# Pedal_board.net
KiCad netlist of a schematic drawn in EAGLE
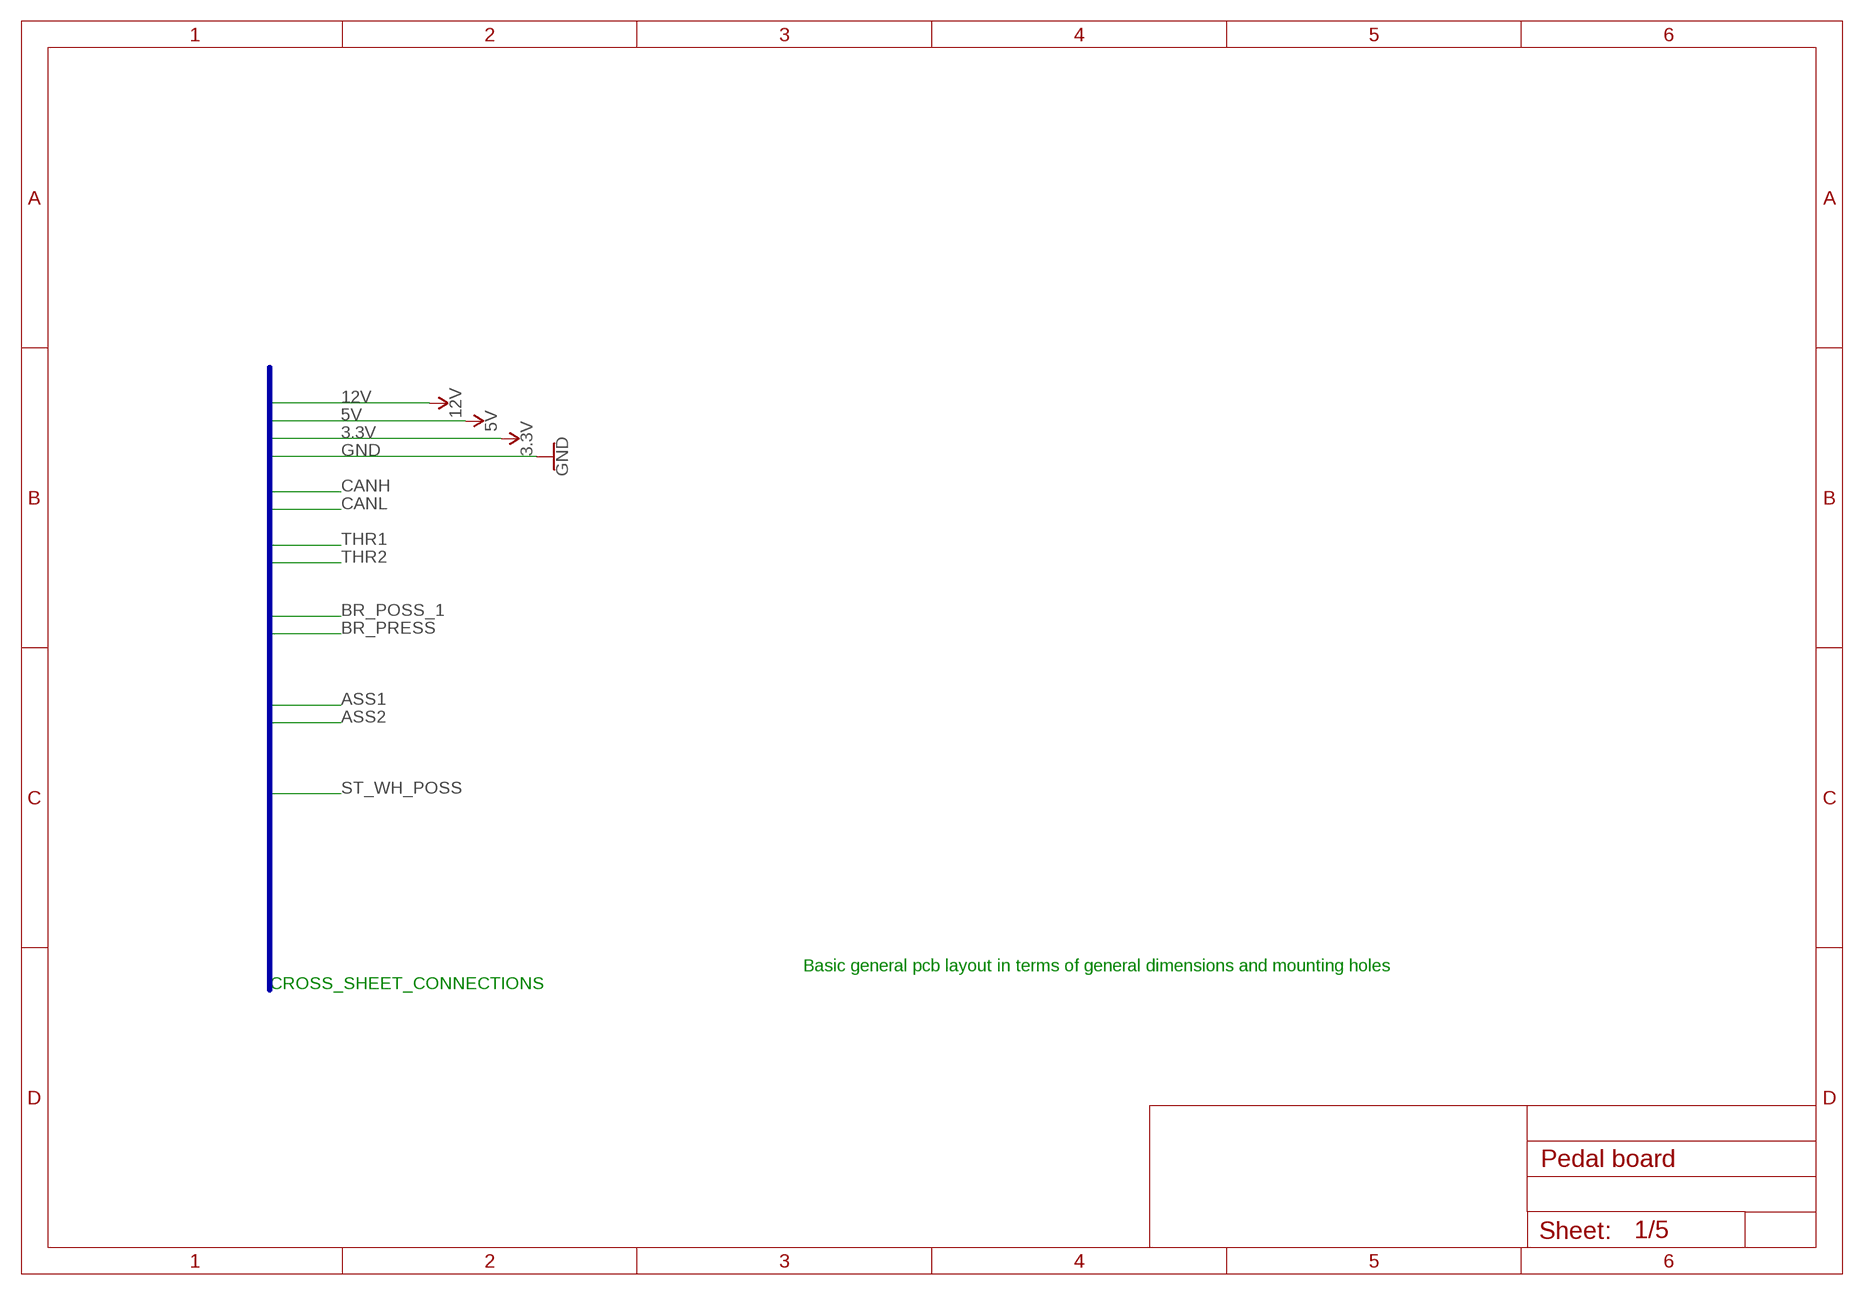
[diagram p0: schematic, sheet 1]
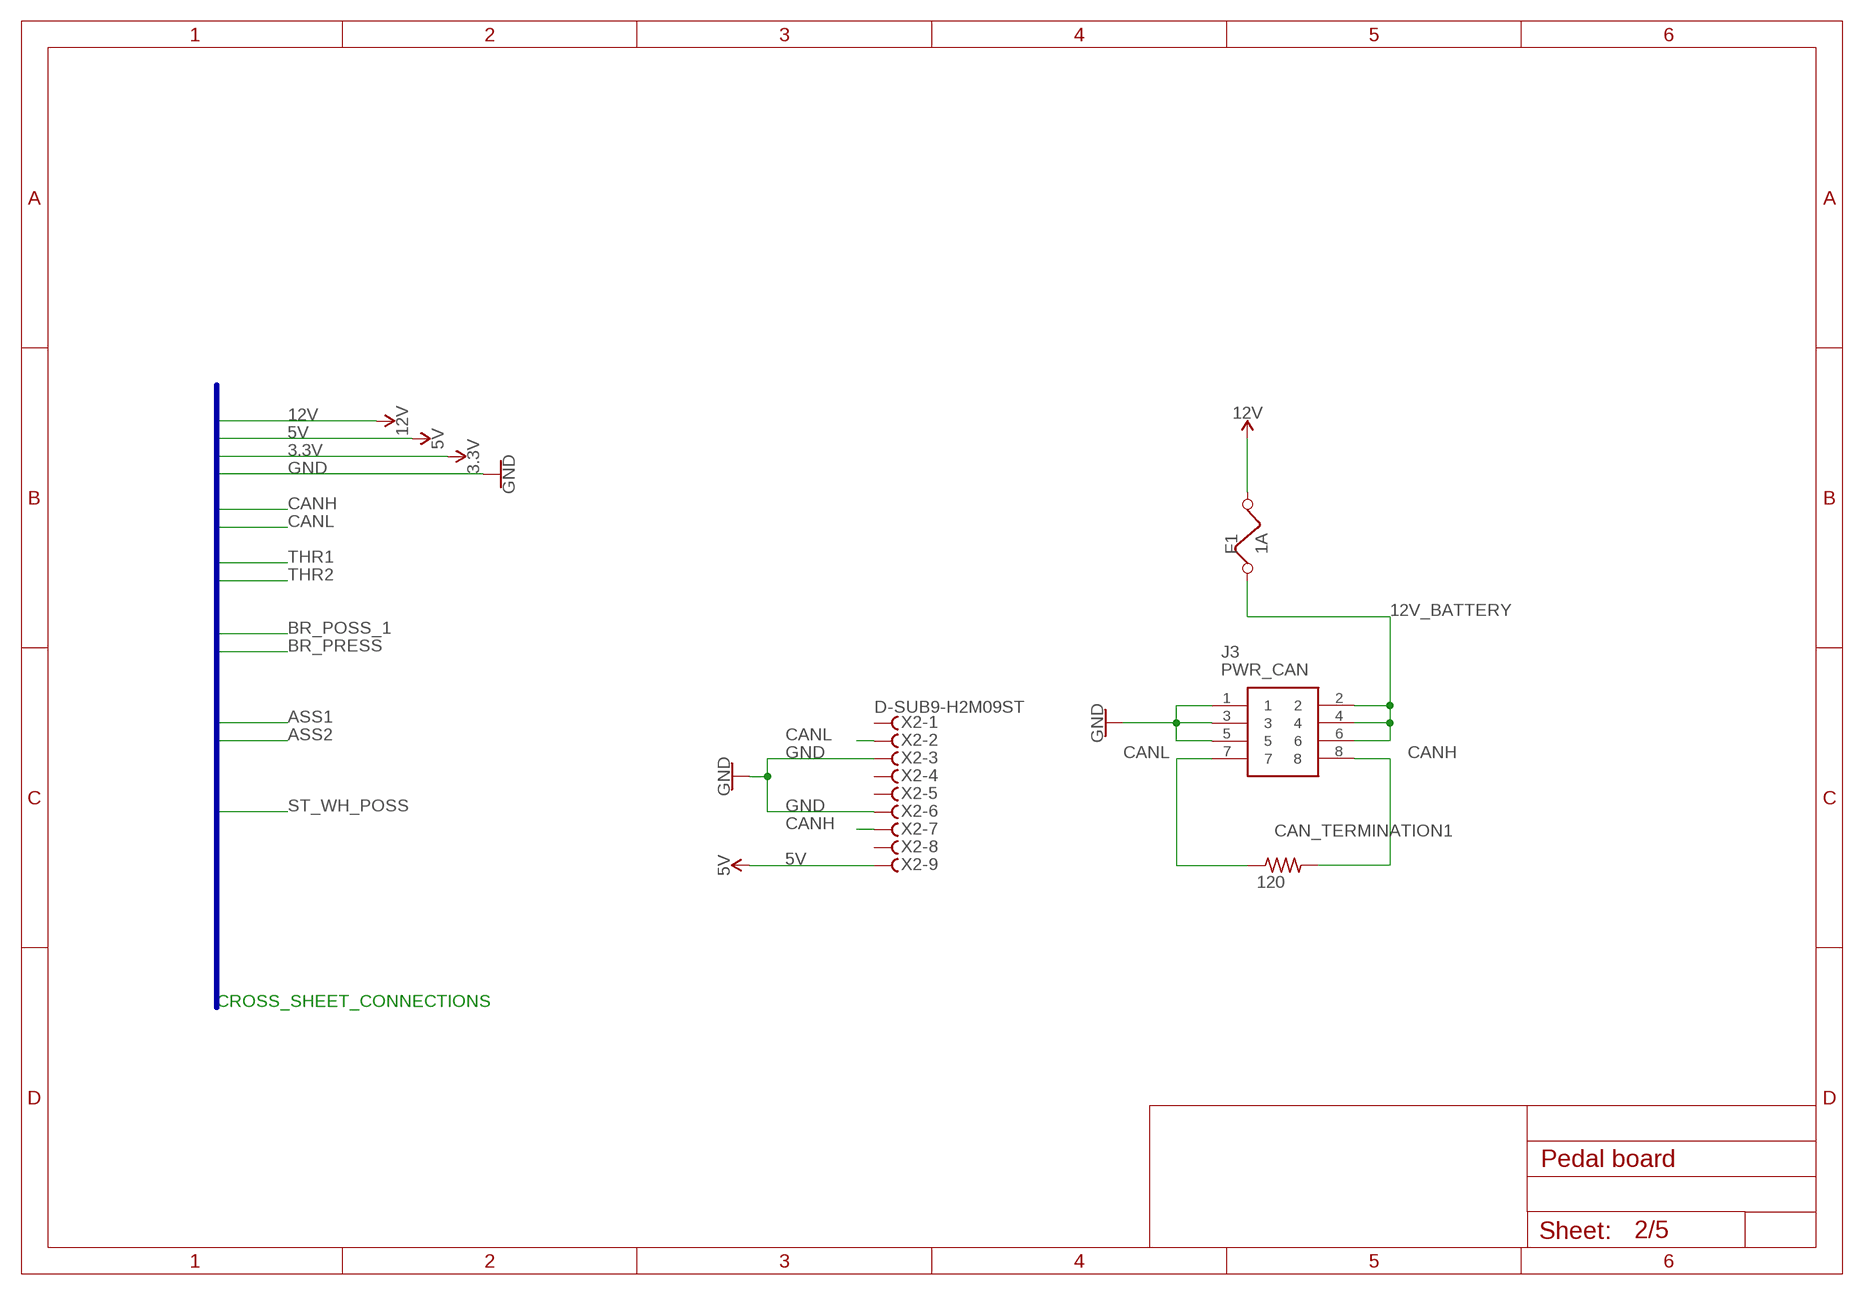
[diagram p1: schematic, sheet 2]
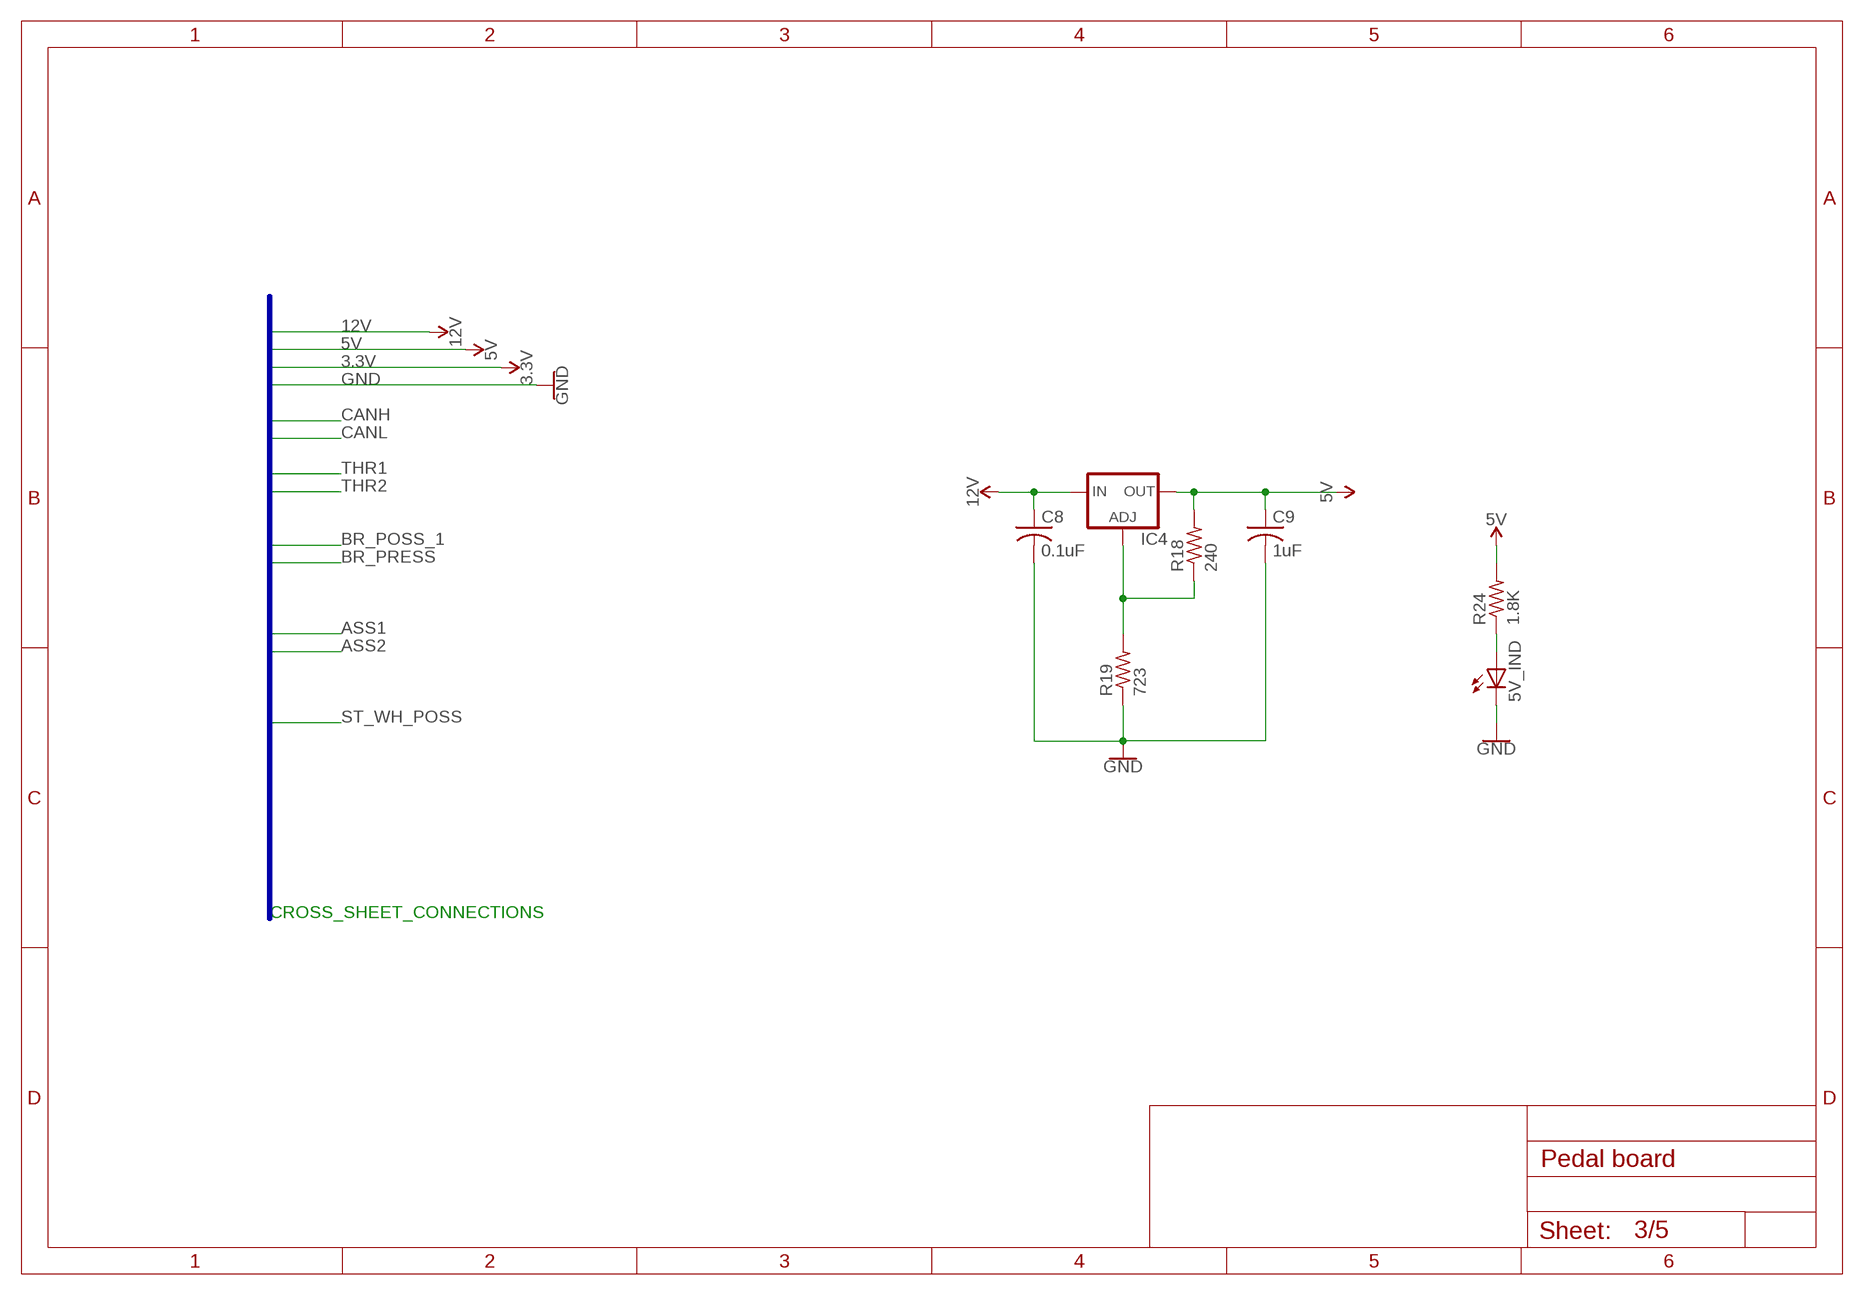
[diagram p2: schematic, sheet 3]
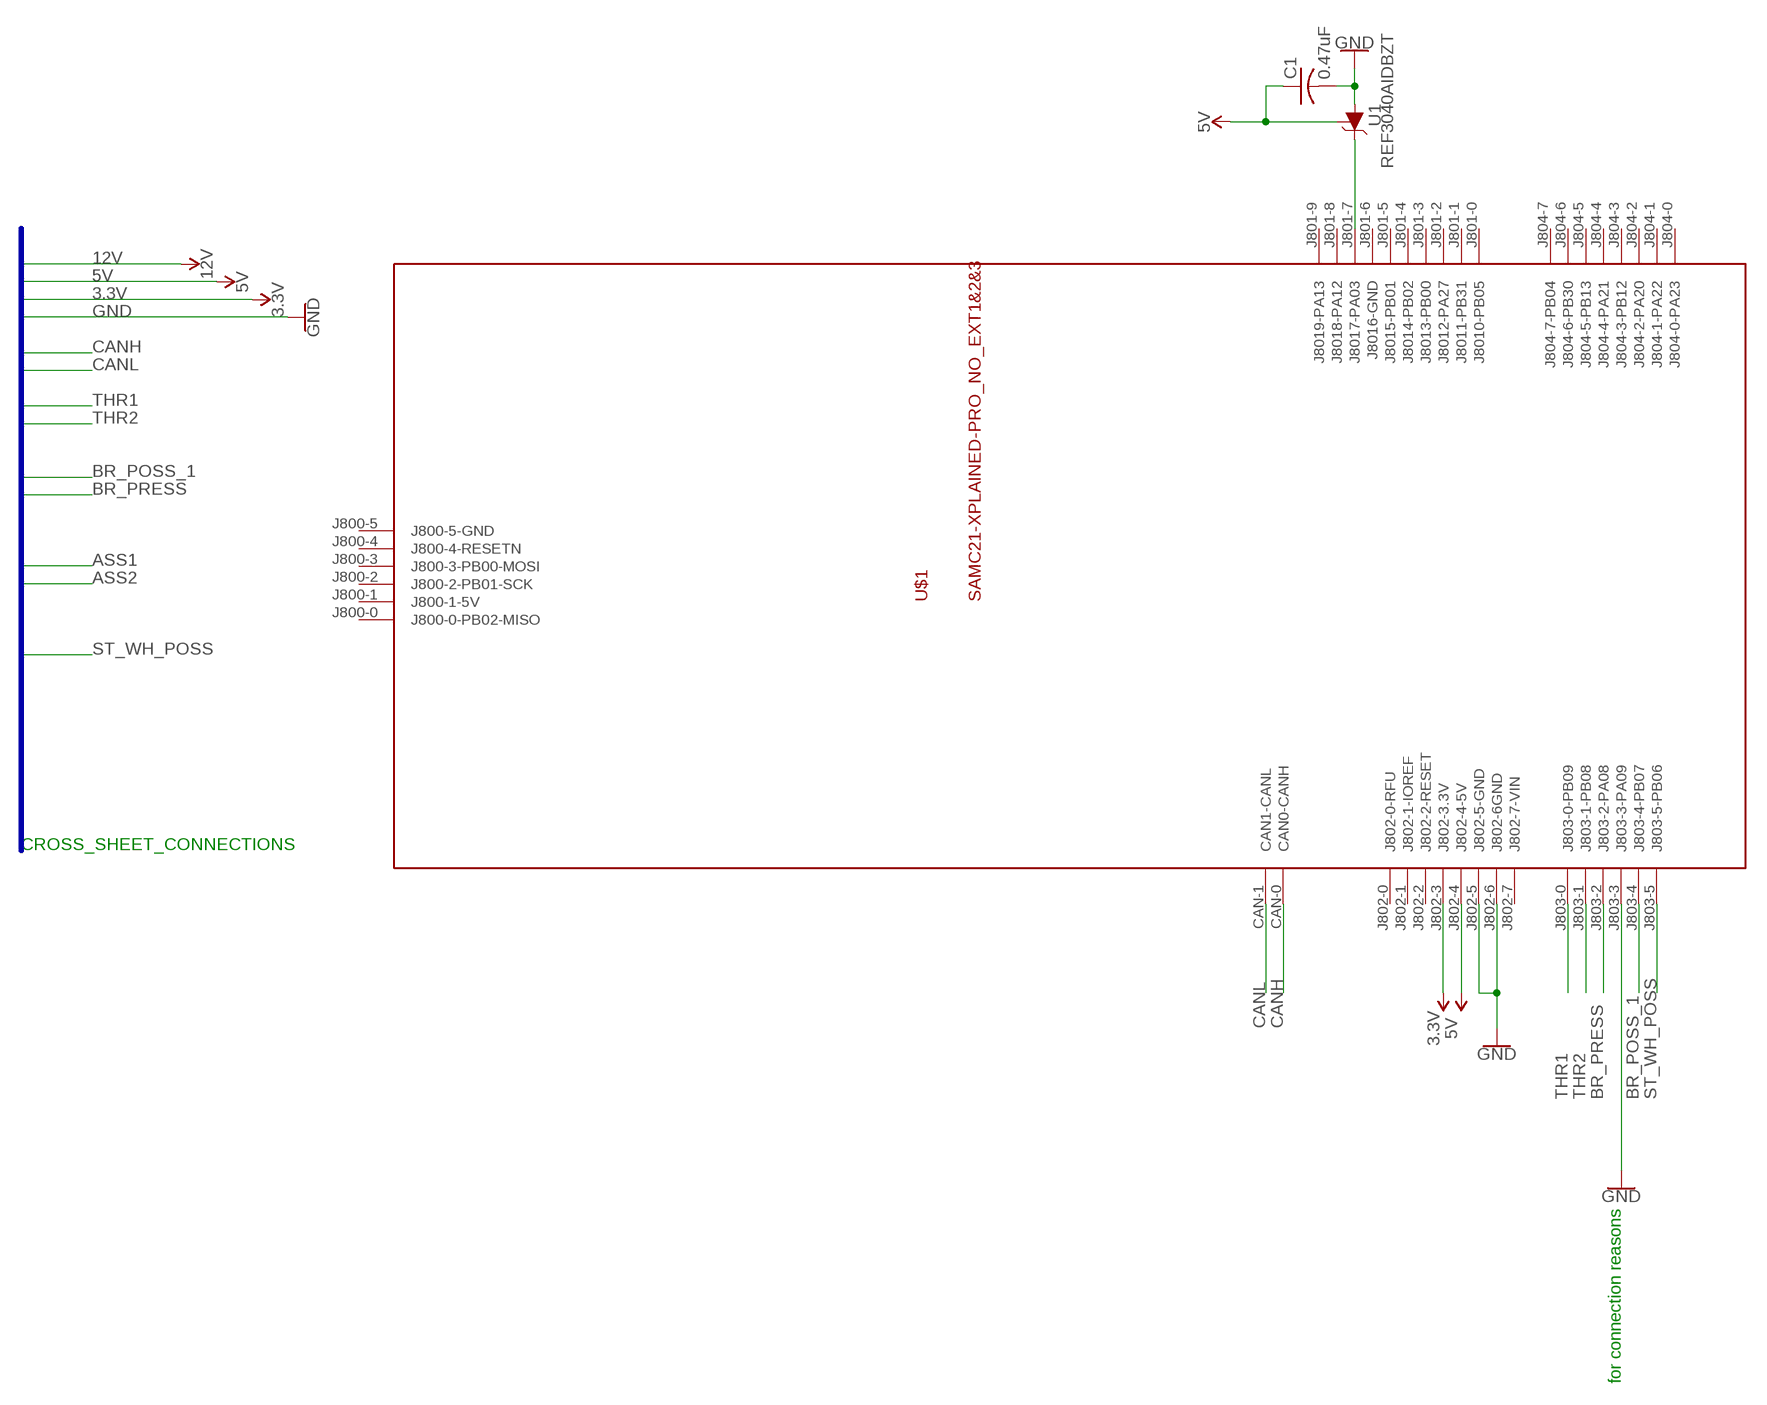
[diagram p3: schematic, sheet 4]
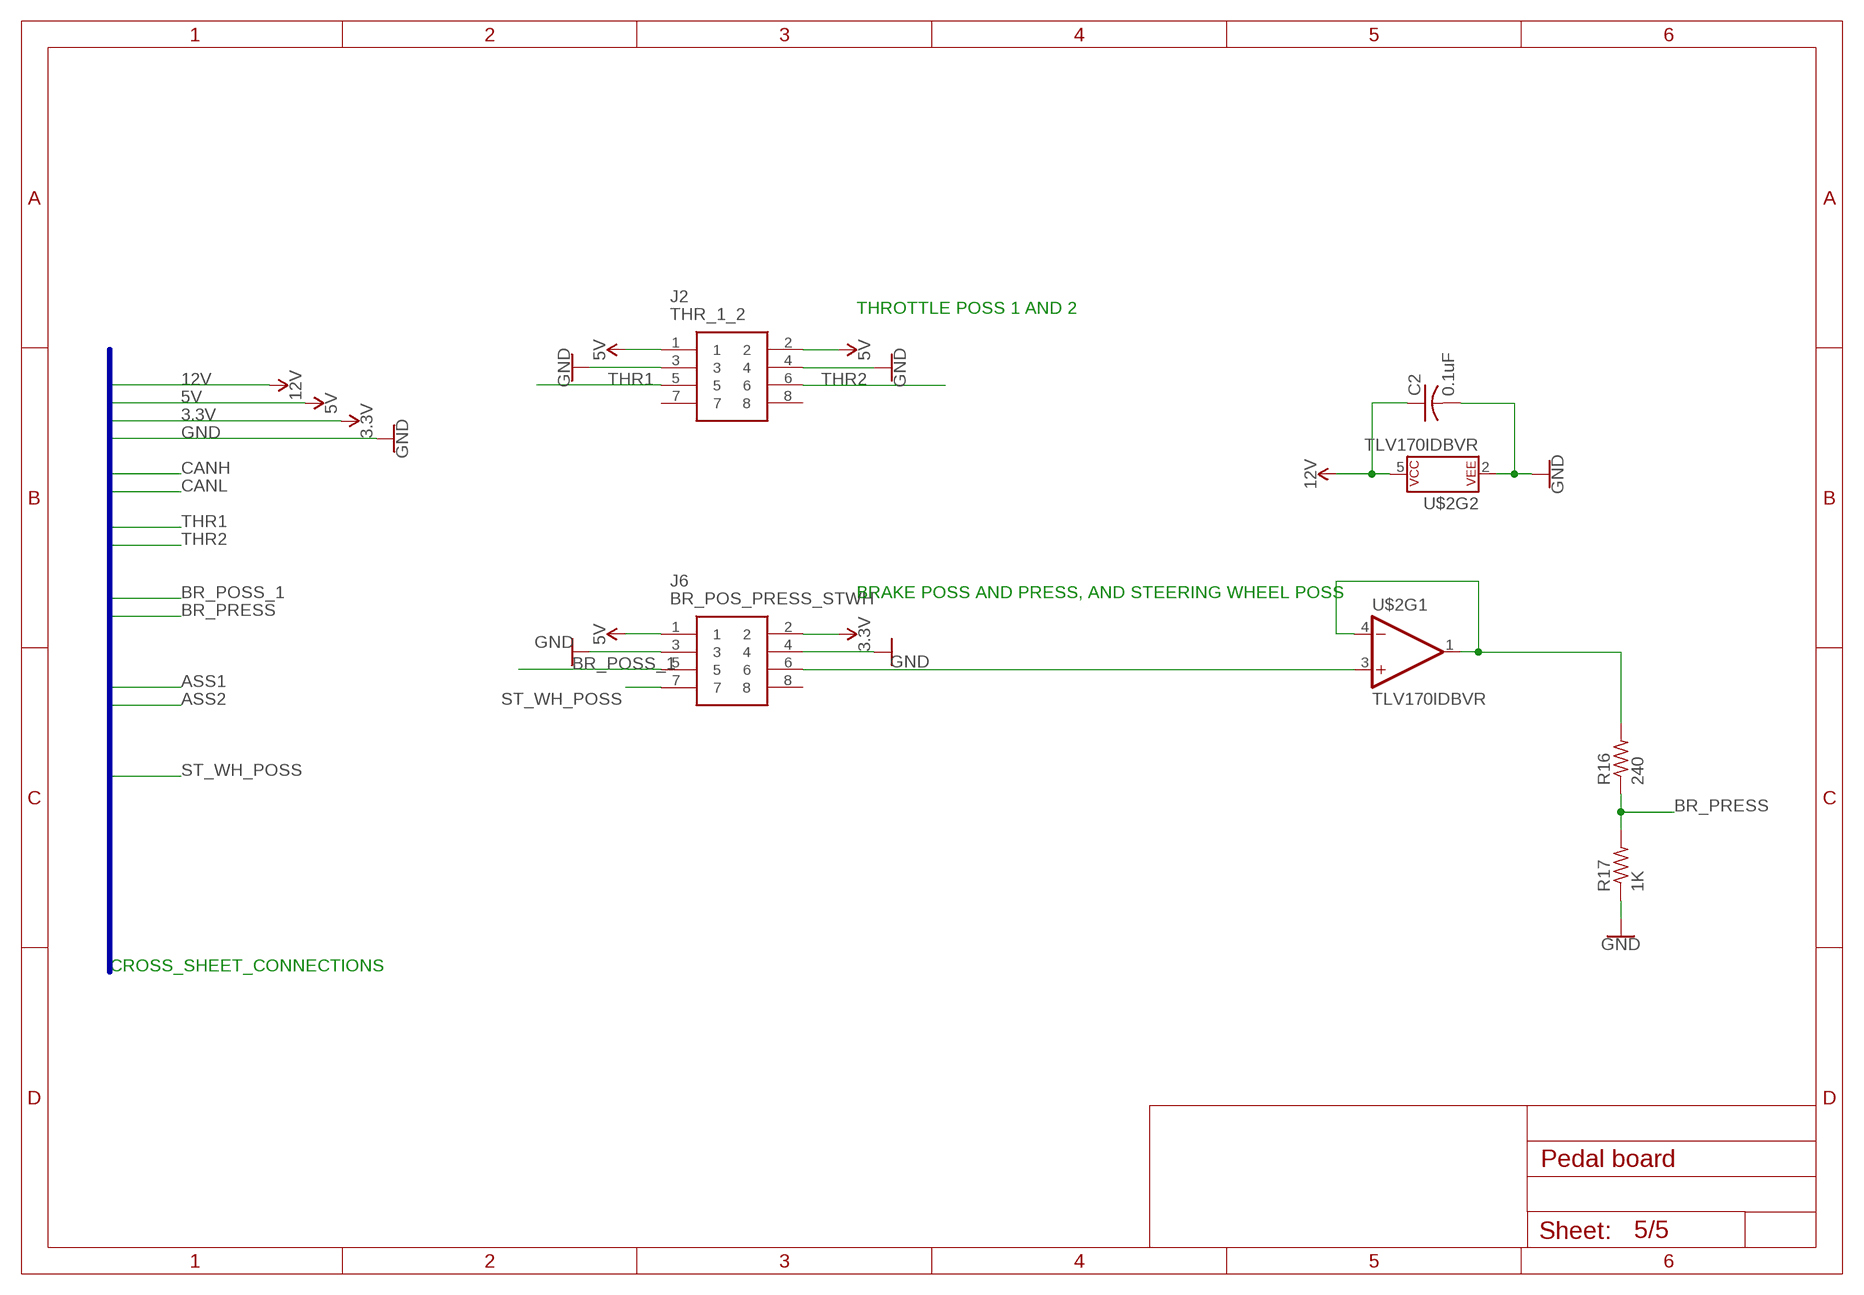
[diagram p4: schematic, sheet 5]

(export (version "E")
  (design (tool "Eeschema 10.0.6"))
  (components
    (comp (ref "5V_IND")
      (value "LED3MM")
      (footprint "eagle-import:LED3MM")
      (libsource (lib "eagle-import") (part "LED3MM"))
    )
    (comp (ref "C8")
      (value "0.1uF")
      (footprint "eagle-import:C050-025X075")
      (libsource (lib "eagle-import") (part "C-US050-025X075"))
    )
    (comp (ref "C9")
      (value "1uF")
      (footprint "eagle-import:C050-025X075")
      (libsource (lib "eagle-import") (part "C-US050-025X075"))
    )
    (comp (ref "IC4")
      (value "LM317TS")
      (footprint "eagle-import:317TS")
      (libsource (lib "eagle-import") (part "LM317TS"))
    )
    (comp (ref "R18")
      (value "240")
      (footprint "eagle-import:R0805")
      (libsource (lib "eagle-import") (part "R-US_R0805"))
    )
    (comp (ref "R19")
      (value "723")
      (footprint "eagle-import:R0805")
      (libsource (lib "eagle-import") (part "R-US_R0805"))
    )
    (comp (ref "R24")
      (value "1.8K")
      (footprint "eagle-import:R0805")
      (libsource (lib "eagle-import") (part "R-US_R0805"))
    )
    (comp (ref "C1")
      (value "0.47uF")
      (footprint "eagle-import:C050-024X044")
      (libsource (lib "eagle-import") (part "C-US050-024X044"))
    )
    (comp (ref "U$1")
      (value "SAMC21-XPLAINED-PRO_NO_EXT1&2&3")
      (footprint "eagle-import:SAMC21-XPLAINED-PRO_NO_EXT1&2&3")
      (libsource (lib "eagle-import") (part "SAMC21-XPLAINED-PRO_NO_EXT1&2&3"))
    )
    (comp (ref "U1")
      (value "REF3040AIDBZT")
      (footprint "eagle-import:SOT23-3")
      (libsource (lib "eagle-import") (part "LM4051"))
    )
    (comp (ref "C2")
      (value "0.1uF")
      (footprint "eagle-import:C050-024X044")
      (libsource (lib "eagle-import") (part "C-US050-024X044"))
    )
    (comp (ref "J2")
      (value "THR_1_2")
      (footprint "eagle-import:HDRV8W64P254_2X4_1778X895X915P")
      (fields
        (field (name "MANUFACTURER_PART_NUMBER") "T821108A1S100CEU")
        (field (name "RS_PART_NUMBER") "1702738")
      )
      (libsource (lib "eagle-import") (part "T821108A1S100CEU"))
    )
    (comp (ref "J6")
      (value "BR_POS_PRESS_STWH")
      (footprint "eagle-import:HDRV8W64P254_2X4_1778X895X915P")
      (fields
        (field (name "MANUFACTURER_PART_NUMBER") "T821108A1S100CEU")
        (field (name "RS_PART_NUMBER") "1702738")
      )
      (libsource (lib "eagle-import") (part "T821108A1S100CEU"))
    )
    (comp (ref "R16")
      (value "240")
      (footprint "eagle-import:R0805")
      (libsource (lib "eagle-import") (part "R-US_R0805"))
    )
    (comp (ref "R17")
      (value "1K")
      (footprint "eagle-import:R0805")
      (libsource (lib "eagle-import") (part "R-US_R0805"))
    )
    (comp (ref "U$2")
      (value "TLV170IDBVR")
      (footprint "eagle-import:SOT23-5")
      (libsource (lib "eagle-import") (part "MCP6021T-E/OT"))
    )
    (comp (ref "CAN_TERMINATION1")
      (value "120")
      (footprint "eagle-import:R0805")
      (libsource (lib "eagle-import") (part "R-US_R0805"))
    )
    (comp (ref "F1")
      (value "1A")
      (footprint "eagle-import:FUSE")
      (libsource (lib "eagle-import") (part "FUSE"))
    )
    (comp (ref "J3")
      (value "PWR_CAN")
      (footprint "eagle-import:HDRV8W64P254_2X4_1778X895X915P")
      (fields
        (field (name "MANUFACTURER_PART_NUMBER") "T821108A1S100CEU")
        (field (name "RS_PART_NUMBER") "1702738")
      )
      (libsource (lib "eagle-import") (part "T821108A1S100CEU"))
    )
    (comp (ref "X2")
      (value "D-SUB9-H2M09ST")
      (footprint "eagle-import:H2M09ST")
      (libsource (lib "eagle-import") (part "D-SUB9-H2M09ST"))
    )
  )
  (nets
    (net (code "1") (name "3.3V") (class "Default")
      (node (ref "J6") (pin "2") (pinfunction "2_2") (pintype "bidirectional"))
      (node (ref "U$1") (pin "J802-3") (pinfunction "J802-3.3V_J802-3") (pintype "bidirectional"))
    )
    (net (code "2") (name "5V") (class "Default")
      (node (ref "C1") (pin "1") (pinfunction "1_1") (pintype "passive"))
      (node (ref "C9") (pin "1") (pinfunction "1_1") (pintype "passive"))
      (node (ref "IC4") (pin "2") (pinfunction "OUT_2") (pintype "passive"))
      (node (ref "J2") (pin "1") (pinfunction "1_1") (pintype "bidirectional"))
      (node (ref "J2") (pin "2") (pinfunction "2_2") (pintype "bidirectional"))
      (node (ref "J6") (pin "1") (pinfunction "1_1") (pintype "bidirectional"))
      (node (ref "R18") (pin "2") (pinfunction "2_2") (pintype "passive"))
      (node (ref "R24") (pin "2") (pinfunction "2_2") (pintype "passive"))
      (node (ref "U$1") (pin "J802-4") (pinfunction "J802-4-5V_J802-4") (pintype "bidirectional"))
      (node (ref "U1") (pin "1") (pinfunction "ADJ_1") (pintype "bidirectional"))
      (node (ref "X2") (pin "9") (pinfunction "F_9") (pintype "passive"))
    )
    (net (code "3") (name "12V") (class "Default")
      (node (ref "C2") (pin "1") (pinfunction "1_1") (pintype "passive"))
      (node (ref "C8") (pin "1") (pinfunction "1_1") (pintype "passive"))
      (node (ref "F1") (pin "2") (pinfunction "2_2") (pintype "passive"))
      (node (ref "IC4") (pin "3") (pinfunction "IN_3") (pintype "input"))
      (node (ref "U$2") (pin "5") (pinfunction "P$V+_5") (pintype "bidirectional"))
    )
    (net (code "4") (name "12V_BATTERY") (class "Default")
      (node (ref "F1") (pin "1") (pinfunction "1_1") (pintype "passive"))
      (node (ref "J3") (pin "2") (pinfunction "2_2") (pintype "bidirectional"))
      (node (ref "J3") (pin "4") (pinfunction "4_4") (pintype "bidirectional"))
      (node (ref "J3") (pin "6") (pinfunction "6_6") (pintype "bidirectional"))
    )
    (net (code "7") (name "BR_POSS_1") (class "Default")
      (node (ref "J6") (pin "5") (pinfunction "5_5") (pintype "bidirectional"))
      (node (ref "U$1") (pin "J803-4") (pinfunction "J803-4-PB07_J803-4") (pintype "bidirectional"))
    )
    (net (code "8") (name "BR_PRESS") (class "Default")
      (node (ref "R16") (pin "1") (pinfunction "1_1") (pintype "passive"))
      (node (ref "R17") (pin "2") (pinfunction "2_2") (pintype "passive"))
      (node (ref "U$1") (pin "J803-2") (pinfunction "J803-2-PA08_J803-2") (pintype "bidirectional"))
    )
    (net (code "9") (name "CANH") (class "Default")
      (node (ref "CAN_TERMINATION1") (pin "2") (pinfunction "2_2") (pintype "passive"))
      (node (ref "J3") (pin "8") (pinfunction "8_8") (pintype "bidirectional"))
      (node (ref "U$1") (pin "CAN-0") (pinfunction "CAN0-CANH_CAN-0") (pintype "bidirectional"))
      (node (ref "X2") (pin "7") (pinfunction "F_7") (pintype "passive"))
    )
    (net (code "10") (name "CANL") (class "Default")
      (node (ref "CAN_TERMINATION1") (pin "1") (pinfunction "1_1") (pintype "passive"))
      (node (ref "J3") (pin "7") (pinfunction "7_7") (pintype "bidirectional"))
      (node (ref "U$1") (pin "CAN-1") (pinfunction "CAN1-CANL_CAN-1") (pintype "bidirectional"))
      (node (ref "X2") (pin "2") (pinfunction "F_2") (pintype "passive"))
    )
    (net (code "11") (name "GND") (class "Default")
      (node (ref "5V_IND") (pin "K") (pinfunction "C_K") (pintype "passive"))
      (node (ref "C1") (pin "2") (pinfunction "2_2") (pintype "passive"))
      (node (ref "C2") (pin "2") (pinfunction "2_2") (pintype "passive"))
      (node (ref "C8") (pin "2") (pinfunction "2_2") (pintype "passive"))
      (node (ref "C9") (pin "2") (pinfunction "2_2") (pintype "passive"))
      (node (ref "J2") (pin "3") (pinfunction "3_3") (pintype "bidirectional"))
      (node (ref "J2") (pin "4") (pinfunction "4_4") (pintype "bidirectional"))
      (node (ref "J3") (pin "1") (pinfunction "1_1") (pintype "bidirectional"))
      (node (ref "J3") (pin "3") (pinfunction "3_3") (pintype "bidirectional"))
      (node (ref "J3") (pin "5") (pinfunction "5_5") (pintype "bidirectional"))
      (node (ref "J6") (pin "3") (pinfunction "3_3") (pintype "bidirectional"))
      (node (ref "J6") (pin "4") (pinfunction "4_4") (pintype "bidirectional"))
      (node (ref "R17") (pin "1") (pinfunction "1_1") (pintype "passive"))
      (node (ref "R19") (pin "1") (pinfunction "1_1") (pintype "passive"))
      (node (ref "U$1") (pin "J802-5") (pinfunction "J802-5-GND_J802-5") (pintype "bidirectional"))
      (node (ref "U$1") (pin "J802-6") (pinfunction "J802-6GND_J802-6") (pintype "bidirectional"))
      (node (ref "U$1") (pin "J803-3") (pinfunction "J803-3-PA09_J803-3") (pintype "bidirectional"))
      (node (ref "U$2") (pin "2") (pinfunction "P$V-_2") (pintype "bidirectional"))
      (node (ref "U1") (pin "3") (pinfunction "A_3") (pintype "passive"))
      (node (ref "X2") (pin "3") (pinfunction "F_3") (pintype "passive"))
      (node (ref "X2") (pin "6") (pinfunction "F_6") (pintype "passive"))
    )
    (net (code "12") (name "Net-(5V_IND-PadA)") (class "Default")
      (node (ref "5V_IND") (pin "A") (pinfunction "A_A") (pintype "passive"))
      (node (ref "R24") (pin "1") (pinfunction "1_1") (pintype "passive"))
    )
    (net (code "13") (name "Net-(IC4-ADJ)") (class "Default")
      (node (ref "IC4") (pin "1") (pinfunction "ADJ_1") (pintype "input"))
      (node (ref "R18") (pin "1") (pinfunction "1_1") (pintype "passive"))
      (node (ref "R19") (pin "2") (pinfunction "2_2") (pintype "passive"))
    )
    (net (code "14") (name "Net-(U$1-J8017-PA03)") (class "Default")
      (node (ref "U$1") (pin "J801-7") (pinfunction "J8017-PA03_J801-7") (pintype "bidirectional"))
      (node (ref "U1") (pin "2") (pinfunction "C_2") (pintype "passive"))
    )
    (net (code "15") (name "Net-(U$2A-+IN)") (class "Default")
      (node (ref "J6") (pin "6") (pinfunction "6_6") (pintype "bidirectional"))
      (node (ref "U$2") (pin "3") (pinfunction "+IN_3") (pintype "input"))
    )
    (net (code "16") (name "Net-(U$2A--IN)") (class "Default")
      (node (ref "R16") (pin "2") (pinfunction "2_2") (pintype "passive"))
      (node (ref "U$2") (pin "1") (pinfunction "OUT_1") (pintype "output"))
      (node (ref "U$2") (pin "4") (pinfunction "-IN_4") (pintype "input"))
    )
    (net (code "17") (name "ST_WH_POSS") (class "Default")
      (node (ref "J6") (pin "7") (pinfunction "7_7") (pintype "bidirectional"))
      (node (ref "U$1") (pin "J803-5") (pinfunction "J803-5-PB06_J803-5") (pintype "bidirectional"))
    )
    (net (code "18") (name "THR1") (class "Default")
      (node (ref "J2") (pin "5") (pinfunction "5_5") (pintype "bidirectional"))
      (node (ref "U$1") (pin "J803-0") (pinfunction "J803-0-PB09_J803-0") (pintype "bidirectional"))
    )
    (net (code "19") (name "THR2") (class "Default")
      (node (ref "J2") (pin "6") (pinfunction "6_6") (pintype "bidirectional"))
      (node (ref "U$1") (pin "J803-1") (pinfunction "J803-1-PB08_J803-1") (pintype "bidirectional"))
    )
    (net (code "20") (name "unconnected-(J2-Pad7)") (class "Default")
      (node (ref "J2") (pin "7") (pinfunction "7_7") (pintype "bidirectional"))
    )
    (net (code "21") (name "unconnected-(J2-Pad8)") (class "Default")
      (node (ref "J2") (pin "8") (pinfunction "8_8") (pintype "bidirectional"))
    )
    (net (code "22") (name "unconnected-(J6-Pad8)") (class "Default")
      (node (ref "J6") (pin "8") (pinfunction "8_8") (pintype "bidirectional"))
    )
    (net (code "23") (name "unconnected-(U$1-J800-0-PB02-MISO-PadJ800-0)") (class "Default")
      (node (ref "U$1") (pin "J800-0") (pinfunction "J800-0-PB02-MISO_J800-0") (pintype "bidirectional"))
    )
    (net (code "24") (name "unconnected-(U$1-J800-1-5V-PadJ800-1)") (class "Default")
      (node (ref "U$1") (pin "J800-1") (pinfunction "J800-1-5V_J800-1") (pintype "bidirectional"))
    )
    (net (code "25") (name "unconnected-(U$1-J800-2-PB01-SCK-PadJ800-2)") (class "Default")
      (node (ref "U$1") (pin "J800-2") (pinfunction "J800-2-PB01-SCK_J800-2") (pintype "bidirectional"))
    )
    (net (code "26") (name "unconnected-(U$1-J800-3-PB00-MOSI-PadJ800-3)") (class "Default")
      (node (ref "U$1") (pin "J800-3") (pinfunction "J800-3-PB00-MOSI_J800-3") (pintype "bidirectional"))
    )
    (net (code "27") (name "unconnected-(U$1-J800-4-RESETN-PadJ800-4)") (class "Default")
      (node (ref "U$1") (pin "J800-4") (pinfunction "J800-4-RESETN_J800-4") (pintype "bidirectional"))
    )
    (net (code "28") (name "unconnected-(U$1-J800-5-GND-PadJ800-5)") (class "Default")
      (node (ref "U$1") (pin "J800-5") (pinfunction "J800-5-GND_J800-5") (pintype "bidirectional"))
    )
    (net (code "29") (name "unconnected-(U$1-J802-0-RFU-PadJ802-0)") (class "Default")
      (node (ref "U$1") (pin "J802-0") (pinfunction "J802-0-RFU_J802-0") (pintype "bidirectional"))
    )
    (net (code "30") (name "unconnected-(U$1-J802-1-IOREF-PadJ802-1)") (class "Default")
      (node (ref "U$1") (pin "J802-1") (pinfunction "J802-1-IOREF_J802-1") (pintype "bidirectional"))
    )
    (net (code "31") (name "unconnected-(U$1-J802-2-RESET-PadJ802-2)") (class "Default")
      (node (ref "U$1") (pin "J802-2") (pinfunction "J802-2-RESET_J802-2") (pintype "bidirectional"))
    )
    (net (code "32") (name "unconnected-(U$1-J802-7-VIN-PadJ802-7)") (class "Default")
      (node (ref "U$1") (pin "J802-7") (pinfunction "J802-7-VIN_J802-7") (pintype "bidirectional"))
    )
    (net (code "33") (name "unconnected-(U$1-J804-0-PA23-PadJ804-0)") (class "Default")
      (node (ref "U$1") (pin "J804-0") (pinfunction "J804-0-PA23_J804-0") (pintype "bidirectional"))
    )
    (net (code "34") (name "unconnected-(U$1-J804-1-PA22-PadJ804-1)") (class "Default")
      (node (ref "U$1") (pin "J804-1") (pinfunction "J804-1-PA22_J804-1") (pintype "bidirectional"))
    )
    (net (code "35") (name "unconnected-(U$1-J804-2-PA20-PadJ804-2)") (class "Default")
      (node (ref "U$1") (pin "J804-2") (pinfunction "J804-2-PA20_J804-2") (pintype "bidirectional"))
    )
    (net (code "36") (name "unconnected-(U$1-J804-3-PB12-PadJ804-3)") (class "Default")
      (node (ref "U$1") (pin "J804-3") (pinfunction "J804-3-PB12_J804-3") (pintype "bidirectional"))
    )
    (net (code "37") (name "unconnected-(U$1-J804-4-PA21-PadJ804-4)") (class "Default")
      (node (ref "U$1") (pin "J804-4") (pinfunction "J804-4-PA21_J804-4") (pintype "bidirectional"))
    )
    (net (code "38") (name "unconnected-(U$1-J804-5-PB13-PadJ804-5)") (class "Default")
      (node (ref "U$1") (pin "J804-5") (pinfunction "J804-5-PB13_J804-5") (pintype "bidirectional"))
    )
    (net (code "39") (name "unconnected-(U$1-J804-6-PB30-PadJ804-6)") (class "Default")
      (node (ref "U$1") (pin "J804-6") (pinfunction "J804-6-PB30_J804-6") (pintype "bidirectional"))
    )
    (net (code "40") (name "unconnected-(U$1-J804-7-PB04-PadJ804-7)") (class "Default")
      (node (ref "U$1") (pin "J804-7") (pinfunction "J804-7-PB04_J804-7") (pintype "bidirectional"))
    )
    (net (code "41") (name "unconnected-(U$1-J8010-PB05-PadJ801-0)") (class "Default")
      (node (ref "U$1") (pin "J801-0") (pinfunction "J8010-PB05_J801-0") (pintype "bidirectional"))
    )
    (net (code "42") (name "unconnected-(U$1-J8011-PB31-PadJ801-1)") (class "Default")
      (node (ref "U$1") (pin "J801-1") (pinfunction "J8011-PB31_J801-1") (pintype "bidirectional"))
    )
    (net (code "43") (name "unconnected-(U$1-J8012-PA27-PadJ801-2)") (class "Default")
      (node (ref "U$1") (pin "J801-2") (pinfunction "J8012-PA27_J801-2") (pintype "bidirectional"))
    )
    (net (code "44") (name "unconnected-(U$1-J8013-PB00-PadJ801-3)") (class "Default")
      (node (ref "U$1") (pin "J801-3") (pinfunction "J8013-PB00_J801-3") (pintype "bidirectional"))
    )
    (net (code "45") (name "unconnected-(U$1-J8014-PB02-PadJ801-4)") (class "Default")
      (node (ref "U$1") (pin "J801-4") (pinfunction "J8014-PB02_J801-4") (pintype "bidirectional"))
    )
    (net (code "46") (name "unconnected-(U$1-J8015-PB01-PadJ801-5)") (class "Default")
      (node (ref "U$1") (pin "J801-5") (pinfunction "J8015-PB01_J801-5") (pintype "bidirectional"))
    )
    (net (code "47") (name "unconnected-(U$1-J8016-GND-PadJ801-6)") (class "Default")
      (node (ref "U$1") (pin "J801-6") (pinfunction "J8016-GND_J801-6") (pintype "bidirectional"))
    )
    (net (code "48") (name "unconnected-(U$1-J8018-PA12-PadJ801-8)") (class "Default")
      (node (ref "U$1") (pin "J801-8") (pinfunction "J8018-PA12_J801-8") (pintype "bidirectional"))
    )
    (net (code "49") (name "unconnected-(U$1-J8019-PA13-PadJ801-9)") (class "Default")
      (node (ref "U$1") (pin "J801-9") (pinfunction "J8019-PA13_J801-9") (pintype "bidirectional"))
    )
    (net (code "50") (name "unconnected-(X2A-F-Pad1)") (class "Default")
      (node (ref "X2") (pin "1") (pinfunction "F_1") (pintype "passive"))
    )
    (net (code "51") (name "unconnected-(X2D-F-Pad4)") (class "Default")
      (node (ref "X2") (pin "4") (pinfunction "F_4") (pintype "passive"))
    )
    (net (code "52") (name "unconnected-(X2E-F-Pad5)") (class "Default")
      (node (ref "X2") (pin "5") (pinfunction "F_5") (pintype "passive"))
    )
    (net (code "53") (name "unconnected-(X2H-F-Pad8)") (class "Default")
      (node (ref "X2") (pin "8") (pinfunction "F_8") (pintype "passive"))
    )
  )
)
